# hv_psu_v100_TESTLOAD.net
KiCad netlist of a schematic drawn in Altium Designer
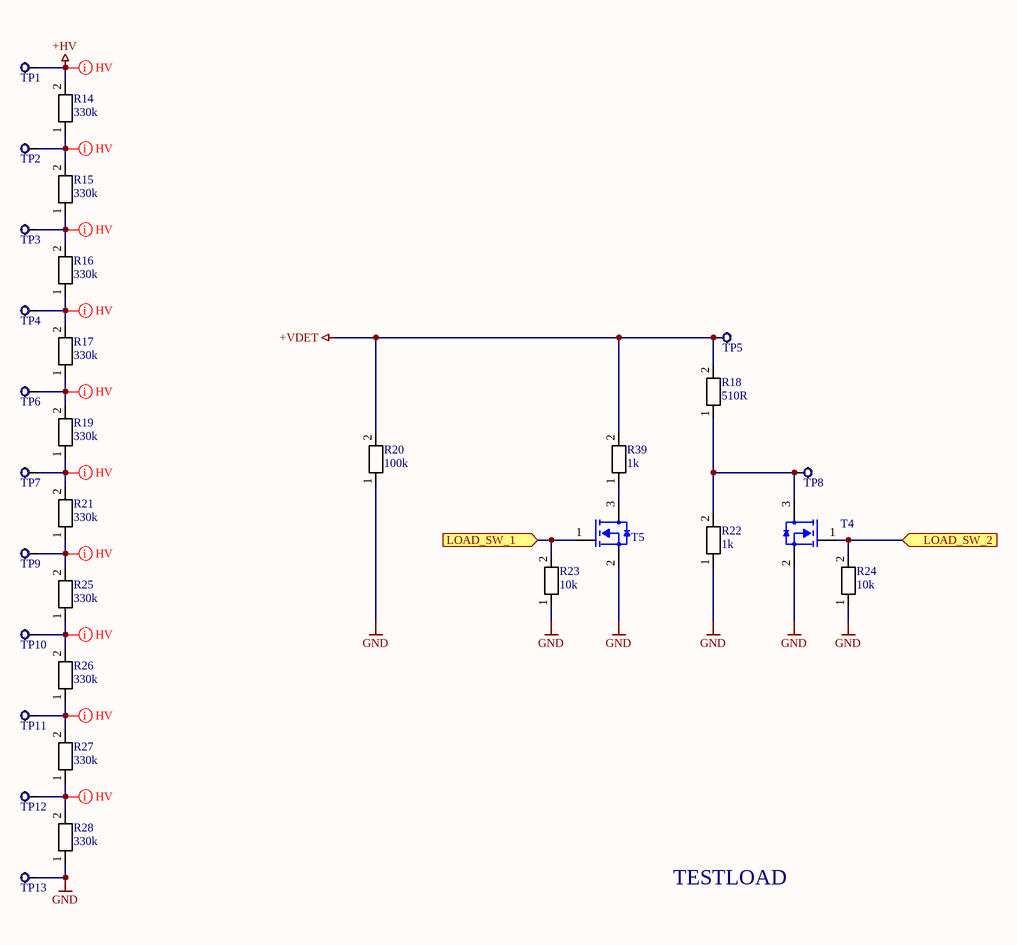
[diagram p0: hv_psu_v100_TESTLOAD.SchDoc]

(export (version "E")
  (design (tool "Eeschema 10.0.6"))
  (components
    (comp (ref "R14") (value "330k") (footprint "1206") (libsource (lib "Schlib1") (part "RESISTOR")))
    (comp (ref "R15") (value "330k") (footprint "1206") (libsource (lib "Schlib1") (part "RESISTOR")))
    (comp (ref "R16") (value "330k") (footprint "1206") (libsource (lib "Schlib1") (part "RESISTOR")))
    (comp (ref "R17") (value "330k") (footprint "1206") (libsource (lib "Schlib1") (part "RESISTOR")))
    (comp (ref "R18") (value "510R") (footprint "1206") (libsource (lib "Schlib1") (part "RESISTOR")))
    (comp (ref "R19") (value "330k") (footprint "1206") (libsource (lib "Schlib1") (part "RESISTOR")))
    (comp (ref "R20") (value "100k") (footprint "1206") (libsource (lib "Schlib1") (part "RESISTOR")))
    (comp (ref "R21") (value "330k") (footprint "1206") (libsource (lib "Schlib1") (part "RESISTOR")))
    (comp (ref "R22") (value "1k") (footprint "1206") (libsource (lib "Schlib1") (part "RESISTOR")))
    (comp (ref "R23") (value "10k") (footprint "1206") (libsource (lib "Schlib1") (part "RESISTOR")))
    (comp (ref "R24") (value "10k") (footprint "1206") (libsource (lib "Schlib1") (part "RESISTOR")))
    (comp (ref "R25") (value "330k") (footprint "1206") (libsource (lib "Schlib1") (part "RESISTOR")))
    (comp (ref "R26") (value "330k") (footprint "1206") (libsource (lib "Schlib1") (part "RESISTOR")))
    (comp (ref "R27") (value "330k") (footprint "1206") (libsource (lib "Schlib1") (part "RESISTOR")))
    (comp (ref "R28") (value "330k") (footprint "1206") (libsource (lib "Schlib1") (part "RESISTOR")))
    (comp (ref "R39") (value "1k") (footprint "1206") (libsource (lib "Schlib1") (part "RESISTOR")))
    (comp (ref "T4")
      (value "MMBF170")
      (footprint "SOT23")
      (description "N MOSFET")
      (libsource (lib "") (part "MMBF170_1"))
    )
    (comp (ref "T5")
      (value "MMBF170")
      (footprint "SOT23")
      (description "N MOSFET")
      (libsource (lib "Schlib1") (part "MMBF170"))
    )
    (comp (ref "TP1") (value "?") (footprint "PAD_40") (libsource (lib "Schlib1") (part "TESTPOINT")))
    (comp (ref "TP2") (value "?") (footprint "PAD_40") (libsource (lib "Schlib1") (part "TESTPOINT")))
    (comp (ref "TP3") (value "?") (footprint "PAD_40") (libsource (lib "Schlib1") (part "TESTPOINT")))
    (comp (ref "TP4") (value "?") (footprint "PAD_40") (libsource (lib "Schlib1") (part "TESTPOINT")))
    (comp (ref "TP5") (value "?") (footprint "PAD_40") (libsource (lib "Schlib1") (part "TESTPOINT")))
    (comp (ref "TP6") (value "?") (footprint "PAD_40") (libsource (lib "Schlib1") (part "TESTPOINT")))
    (comp (ref "TP7") (value "?") (footprint "PAD_40") (libsource (lib "Schlib1") (part "TESTPOINT")))
    (comp (ref "TP8") (value "?") (footprint "PAD_40") (libsource (lib "Schlib1") (part "TESTPOINT")))
    (comp (ref "TP9") (value "?") (footprint "PAD_40") (libsource (lib "Schlib1") (part "TESTPOINT")))
    (comp (ref "TP10") (value "?") (footprint "PAD_40") (libsource (lib "Schlib1") (part "TESTPOINT")))
    (comp (ref "TP11") (value "?") (footprint "PAD_40") (libsource (lib "Schlib1") (part "TESTPOINT")))
    (comp (ref "TP12") (value "?") (footprint "PAD_40") (libsource (lib "Schlib1") (part "TESTPOINT")))
    (comp (ref "TP13") (value "?") (footprint "PAD_40") (libsource (lib "Schlib1") (part "TESTPOINT")))
  )
  (nets
    (net (code "1") (name "+HV") (class "Default")
      (node (ref "R14") (pin "2") (pinfunction "1_2") (pintype "passive"))
      (node (ref "TP1") (pin "1") (pinfunction "1_1") (pintype "passive"))
    )
    (net (code "2") (name "+VDET") (class "Default")
      (node (ref "R18") (pin "2") (pinfunction "1_2") (pintype "passive"))
      (node (ref "R20") (pin "2") (pinfunction "1_2") (pintype "passive"))
      (node (ref "R39") (pin "2") (pinfunction "1_2") (pintype "passive"))
      (node (ref "TP5") (pin "1") (pinfunction "1_1") (pintype "passive"))
    )
    (net (code "3") (name "/LOAD_SW_1") (class "Default")
      (node (ref "R23") (pin "2") (pinfunction "1_2") (pintype "passive"))
      (node (ref "T5") (pin "1") (pinfunction "Gate_1") (pintype "passive"))
    )
    (net (code "4") (name "/LOAD_SW_2") (class "Default")
      (node (ref "R24") (pin "2") (pinfunction "1_2") (pintype "passive"))
      (node (ref "T4") (pin "1") (pinfunction "Gate_1") (pintype "passive"))
    )
    (net (code "5") (name "GND") (class "Default")
      (node (ref "R20") (pin "1") (pinfunction "0_1") (pintype "passive"))
      (node (ref "R22") (pin "1") (pinfunction "0_1") (pintype "passive"))
      (node (ref "R23") (pin "1") (pinfunction "0_1") (pintype "passive"))
      (node (ref "R24") (pin "1") (pinfunction "0_1") (pintype "passive"))
      (node (ref "R28") (pin "1") (pinfunction "0_1") (pintype "passive"))
      (node (ref "T4") (pin "2") (pinfunction "Source_2") (pintype "passive"))
      (node (ref "T5") (pin "2") (pinfunction "Source_2") (pintype "passive"))
      (node (ref "TP13") (pin "1") (pinfunction "1_1") (pintype "passive"))
    )
    (net (code "6") (name "Net-(R14-0)") (class "Default")
      (node (ref "R14") (pin "1") (pinfunction "0_1") (pintype "passive"))
      (node (ref "R15") (pin "2") (pinfunction "1_2") (pintype "passive"))
      (node (ref "TP2") (pin "1") (pinfunction "1_1") (pintype "passive"))
    )
    (net (code "7") (name "Net-(R15-0)") (class "Default")
      (node (ref "R15") (pin "1") (pinfunction "0_1") (pintype "passive"))
      (node (ref "R16") (pin "2") (pinfunction "1_2") (pintype "passive"))
      (node (ref "TP3") (pin "1") (pinfunction "1_1") (pintype "passive"))
    )
    (net (code "8") (name "Net-(R16-0)") (class "Default")
      (node (ref "R16") (pin "1") (pinfunction "0_1") (pintype "passive"))
      (node (ref "R17") (pin "2") (pinfunction "1_2") (pintype "passive"))
      (node (ref "TP4") (pin "1") (pinfunction "1_1") (pintype "passive"))
    )
    (net (code "9") (name "Net-(R17-0)") (class "Default")
      (node (ref "R17") (pin "1") (pinfunction "0_1") (pintype "passive"))
      (node (ref "R19") (pin "2") (pinfunction "1_2") (pintype "passive"))
      (node (ref "TP6") (pin "1") (pinfunction "1_1") (pintype "passive"))
    )
    (net (code "10") (name "Net-(R18-0)") (class "Default")
      (node (ref "R18") (pin "1") (pinfunction "0_1") (pintype "passive"))
      (node (ref "R22") (pin "2") (pinfunction "1_2") (pintype "passive"))
      (node (ref "T4") (pin "3") (pinfunction "Drain_3") (pintype "passive"))
      (node (ref "TP8") (pin "1") (pinfunction "1_1") (pintype "passive"))
    )
    (net (code "11") (name "Net-(R19-0)") (class "Default")
      (node (ref "R19") (pin "1") (pinfunction "0_1") (pintype "passive"))
      (node (ref "R21") (pin "2") (pinfunction "1_2") (pintype "passive"))
      (node (ref "TP7") (pin "1") (pinfunction "1_1") (pintype "passive"))
    )
    (net (code "12") (name "Net-(R21-0)") (class "Default")
      (node (ref "R21") (pin "1") (pinfunction "0_1") (pintype "passive"))
      (node (ref "R25") (pin "2") (pinfunction "1_2") (pintype "passive"))
      (node (ref "TP9") (pin "1") (pinfunction "1_1") (pintype "passive"))
    )
    (net (code "13") (name "Net-(R25-0)") (class "Default")
      (node (ref "R25") (pin "1") (pinfunction "0_1") (pintype "passive"))
      (node (ref "R26") (pin "2") (pinfunction "1_2") (pintype "passive"))
      (node (ref "TP10") (pin "1") (pinfunction "1_1") (pintype "passive"))
    )
    (net (code "14") (name "Net-(R26-0)") (class "Default")
      (node (ref "R26") (pin "1") (pinfunction "0_1") (pintype "passive"))
      (node (ref "R27") (pin "2") (pinfunction "1_2") (pintype "passive"))
      (node (ref "TP11") (pin "1") (pinfunction "1_1") (pintype "passive"))
    )
    (net (code "15") (name "Net-(R27-0)") (class "Default")
      (node (ref "R27") (pin "1") (pinfunction "0_1") (pintype "passive"))
      (node (ref "R28") (pin "2") (pinfunction "1_2") (pintype "passive"))
      (node (ref "TP12") (pin "1") (pinfunction "1_1") (pintype "passive"))
    )
    (net (code "16") (name "Net-(R39-0)") (class "Default")
      (node (ref "R39") (pin "1") (pinfunction "0_1") (pintype "passive"))
      (node (ref "T5") (pin "3") (pinfunction "Drain_3") (pintype "passive"))
    )
  )
)
